# ins_node.net
KiCad netlist of a schematic drawn in EAGLE
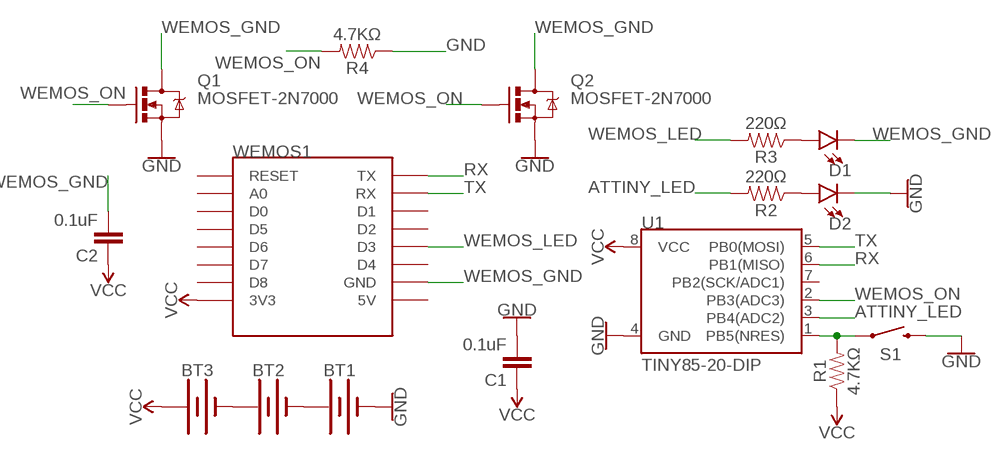
[diagram p0: schematic, sheet 1]

(export (version "E")
  (design (tool "Eeschema 10.0.6"))
  (components
    (comp (ref "BT1")
      (value "BATTERY-AAA")
      (footprint "eagle-import:BATTERY-AAA")
      (libsource (lib "eagle-import") (part "BATTERY-AAA"))
    )
    (comp (ref "BT2")
      (value "BATTERY-AAA")
      (footprint "eagle-import:BATTERY-AAA")
      (libsource (lib "eagle-import") (part "BATTERY-AAA"))
    )
    (comp (ref "BT3")
      (value "BATTERY-AAA")
      (footprint "eagle-import:BATTERY-AAA")
      (libsource (lib "eagle-import") (part "BATTERY-AAA"))
    )
    (comp (ref "C1")
      (value "0.1uF")
      (footprint "eagle-import:CAP-PTH-SMALL-KIT")
      (libsource (lib "eagle-import") (part "0.1UF-KIT-EZ-50V-20%"))
    )
    (comp (ref "C2")
      (value "0.1uF")
      (footprint "eagle-import:CAP-PTH-SMALL-KIT")
      (libsource (lib "eagle-import") (part "0.1UF-KIT-EZ-50V-20%"))
    )
    (comp (ref "D1")
      (value "LED5MM-KIT")
      (footprint "eagle-import:LED_5MM-KIT")
      (libsource (lib "eagle-import") (part "LED5MM-KIT"))
    )
    (comp (ref "D2")
      (value "LED5MM-KIT")
      (footprint "eagle-import:LED_5MM-KIT")
      (libsource (lib "eagle-import") (part "LED5MM-KIT"))
    )
    (comp (ref "Q1")
      (value "MOSFET-2N7000")
      (footprint "eagle-import:TO-92")
      (libsource (lib "eagle-import") (part "MOSFET-NCHANNEL2N7000"))
    )
    (comp (ref "Q2")
      (value "MOSFET-2N7000")
      (footprint "eagle-import:TO-92")
      (libsource (lib "eagle-import") (part "MOSFET-NCHANNEL2N7000"))
    )
    (comp (ref "R1")
      (value "4.7KΩ")
      (footprint "eagle-import:AXIAL-0.3")
      (libsource (lib "eagle-import") (part "RESISTORAXIAL-0.3"))
    )
    (comp (ref "R2")
      (value "220Ω")
      (footprint "eagle-import:AXIAL-0.3")
      (libsource (lib "eagle-import") (part "RESISTORAXIAL-0.3"))
    )
    (comp (ref "R3")
      (value "220Ω")
      (footprint "eagle-import:AXIAL-0.3")
      (libsource (lib "eagle-import") (part "RESISTORAXIAL-0.3"))
    )
    (comp (ref "R4")
      (value "4.7KΩ")
      (footprint "eagle-import:AXIAL-0.3")
      (libsource (lib "eagle-import") (part "RESISTORAXIAL-0.3"))
    )
    (comp (ref "S1")
      (value "MOMENTARY-SWITCH-SPST-PTH-6.0MM")
      (footprint "eagle-import:TACTILE_SWITCH_PTH_6.0MM")
      (libsource (lib "eagle-import") (part "MOMENTARY-SWITCH-SPST-PTH-6.0MM"))
    )
    (comp (ref "U1")
      (value "TINY85-20-DIP")
      (footprint "eagle-import:DIP08_MCU")
      (libsource (lib "eagle-import") (part "ATTINY45TINY85-20-DIP"))
    )
    (comp (ref "WEMOS1")
      (value "WEMOS-D1-MINI")
      (footprint "eagle-import:WEMOS-D1-MINI")
      (libsource (lib "eagle-import") (part "WEMOS-D1-MINI"))
    )
  )
  (nets
    (net (code "1") (name "/ATTINY_LED") (class "Default")
      (node (ref "R2") (pin "P$2") (pinfunction "2_P$2") (pintype "passive"))
      (node (ref "U1") (pin "3") (pinfunction "PB4(ADC2)_3") (pintype "bidirectional"))
    )
    (net (code "2") (name "/RX") (class "Default")
      (node (ref "U1") (pin "6") (pinfunction "PB1(MISO)_6") (pintype "bidirectional"))
      (node (ref "WEMOS1") (pin "TX") (pinfunction "TX_TX") (pintype "bidirectional"))
    )
    (net (code "3") (name "/TX") (class "Default")
      (node (ref "U1") (pin "5") (pinfunction "PB0(MOSI)_5") (pintype "bidirectional"))
      (node (ref "WEMOS1") (pin "RX") (pinfunction "RX_RX") (pintype "bidirectional"))
    )
    (net (code "4") (name "/WEMOS_GND") (class "Default")
      (node (ref "C2") (pin "2") (pinfunction "2_2") (pintype "passive"))
      (node (ref "D1") (pin "K") (pinfunction "C_K") (pintype "passive"))
      (node (ref "Q1") (pin "3") (pinfunction "D_3") (pintype "passive"))
      (node (ref "Q2") (pin "3") (pinfunction "D_3") (pintype "passive"))
      (node (ref "WEMOS1") (pin "GND") (pinfunction "GND_GND") (pintype "bidirectional"))
    )
    (net (code "5") (name "/WEMOS_LED") (class "Default")
      (node (ref "R3") (pin "P$2") (pinfunction "2_P$2") (pintype "passive"))
      (node (ref "WEMOS1") (pin "D3") (pinfunction "D3_D3") (pintype "bidirectional"))
    )
    (net (code "6") (name "/WEMOS_ON") (class "Default")
      (node (ref "Q1") (pin "2") (pinfunction "G_2") (pintype "passive"))
      (node (ref "Q2") (pin "2") (pinfunction "G_2") (pintype "passive"))
      (node (ref "R4") (pin "P$2") (pinfunction "2_P$2") (pintype "passive"))
      (node (ref "U1") (pin "2") (pinfunction "PB3(ADC3)_2") (pintype "bidirectional"))
    )
    (net (code "7") (name "GND") (class "Default")
      (node (ref "BT1") (pin "GND@1") (pinfunction "-_GND@1") (pintype "power_in"))
      (node (ref "C1") (pin "2") (pinfunction "2_2") (pintype "passive"))
      (node (ref "D2") (pin "K") (pinfunction "C_K") (pintype "passive"))
      (node (ref "Q1") (pin "1") (pinfunction "S_1") (pintype "passive"))
      (node (ref "Q2") (pin "1") (pinfunction "S_1") (pintype "passive"))
      (node (ref "R4") (pin "P$1") (pinfunction "1_P$1") (pintype "passive"))
      (node (ref "S1") (pin "3") (pinfunction "2_3") (pintype "passive"))
      (node (ref "U1") (pin "4") (pinfunction "GND_4") (pintype "bidirectional"))
    )
    (net (code "8") (name "Net-(BT1-+)") (class "Default")
      (node (ref "BT1") (pin "PWR@1") (pinfunction "+_PWR@1") (pintype "power_in"))
      (node (ref "BT2") (pin "GND@1") (pinfunction "-_GND@1") (pintype "power_in"))
    )
    (net (code "9") (name "Net-(BT2-+)") (class "Default")
      (node (ref "BT2") (pin "PWR@1") (pinfunction "+_PWR@1") (pintype "power_in"))
      (node (ref "BT3") (pin "GND@1") (pinfunction "-_GND@1") (pintype "power_in"))
    )
    (net (code "10") (name "Net-(R1-2)") (class "Default")
      (node (ref "R1") (pin "P$2") (pinfunction "2_P$2") (pintype "passive"))
      (node (ref "S1") (pin "1") (pinfunction "1_1") (pintype "passive"))
      (node (ref "U1") (pin "1") (pinfunction "PB5(NRES)_1") (pintype "bidirectional"))
    )
    (net (code "11") (name "Net-(R2-1)") (class "Default")
      (node (ref "D2") (pin "A") (pinfunction "A_A") (pintype "passive"))
      (node (ref "R2") (pin "P$1") (pinfunction "1_P$1") (pintype "passive"))
    )
    (net (code "12") (name "Net-(R3-1)") (class "Default")
      (node (ref "D1") (pin "A") (pinfunction "A_A") (pintype "passive"))
      (node (ref "R3") (pin "P$1") (pinfunction "1_P$1") (pintype "passive"))
    )
    (net (code "13") (name "VCC") (class "Default")
      (node (ref "BT3") (pin "PWR@1") (pinfunction "+_PWR@1") (pintype "power_in"))
      (node (ref "C1") (pin "1") (pinfunction "1_1") (pintype "passive"))
      (node (ref "C2") (pin "1") (pinfunction "1_1") (pintype "passive"))
      (node (ref "R1") (pin "P$1") (pinfunction "1_P$1") (pintype "passive"))
      (node (ref "U1") (pin "8") (pinfunction "VCC_8") (pintype "bidirectional"))
      (node (ref "WEMOS1") (pin "3V3") (pinfunction "3V3_3V3") (pintype "bidirectional"))
    )
    (net (code "14") (name "unconnected-(U1-PB2(SCK{slash}ADC1)-Pad7)") (class "Default")
      (node (ref "U1") (pin "7") (pinfunction "PB2(SCK/ADC1)_7") (pintype "bidirectional"))
    )
    (net (code "15") (name "unconnected-(WEMOS1-Pad5V)") (class "Default")
      (node (ref "WEMOS1") (pin "5V") (pinfunction "5V_5V") (pintype "bidirectional"))
    )
    (net (code "16") (name "unconnected-(WEMOS1-PadA0)") (class "Default")
      (node (ref "WEMOS1") (pin "A0") (pinfunction "A0_A0") (pintype "bidirectional"))
    )
    (net (code "17") (name "unconnected-(WEMOS1-PadD0)") (class "Default")
      (node (ref "WEMOS1") (pin "D0") (pinfunction "D0_D0") (pintype "bidirectional"))
    )
    (net (code "18") (name "unconnected-(WEMOS1-PadD1)") (class "Default")
      (node (ref "WEMOS1") (pin "D1") (pinfunction "D1_D1") (pintype "bidirectional"))
    )
    (net (code "19") (name "unconnected-(WEMOS1-PadD2)") (class "Default")
      (node (ref "WEMOS1") (pin "D2") (pinfunction "D2_D2") (pintype "bidirectional"))
    )
    (net (code "20") (name "unconnected-(WEMOS1-PadD4)") (class "Default")
      (node (ref "WEMOS1") (pin "D4") (pinfunction "D4_D4") (pintype "bidirectional"))
    )
    (net (code "21") (name "unconnected-(WEMOS1-PadD5)") (class "Default")
      (node (ref "WEMOS1") (pin "D5") (pinfunction "D5_D5") (pintype "bidirectional"))
    )
    (net (code "22") (name "unconnected-(WEMOS1-PadD6)") (class "Default")
      (node (ref "WEMOS1") (pin "D6") (pinfunction "D6_D6") (pintype "bidirectional"))
    )
    (net (code "23") (name "unconnected-(WEMOS1-PadD7)") (class "Default")
      (node (ref "WEMOS1") (pin "D7") (pinfunction "D7_D7") (pintype "bidirectional"))
    )
    (net (code "24") (name "unconnected-(WEMOS1-PadD8)") (class "Default")
      (node (ref "WEMOS1") (pin "D8") (pinfunction "D8_D8") (pintype "bidirectional"))
    )
    (net (code "25") (name "unconnected-(WEMOS1-PadRESET)") (class "Default")
      (node (ref "WEMOS1") (pin "RESET") (pinfunction "RESET_RESET") (pintype "bidirectional"))
    )
  )
)
